# shinobi_environment.net
KiCad netlist of a schematic drawn in EAGLE
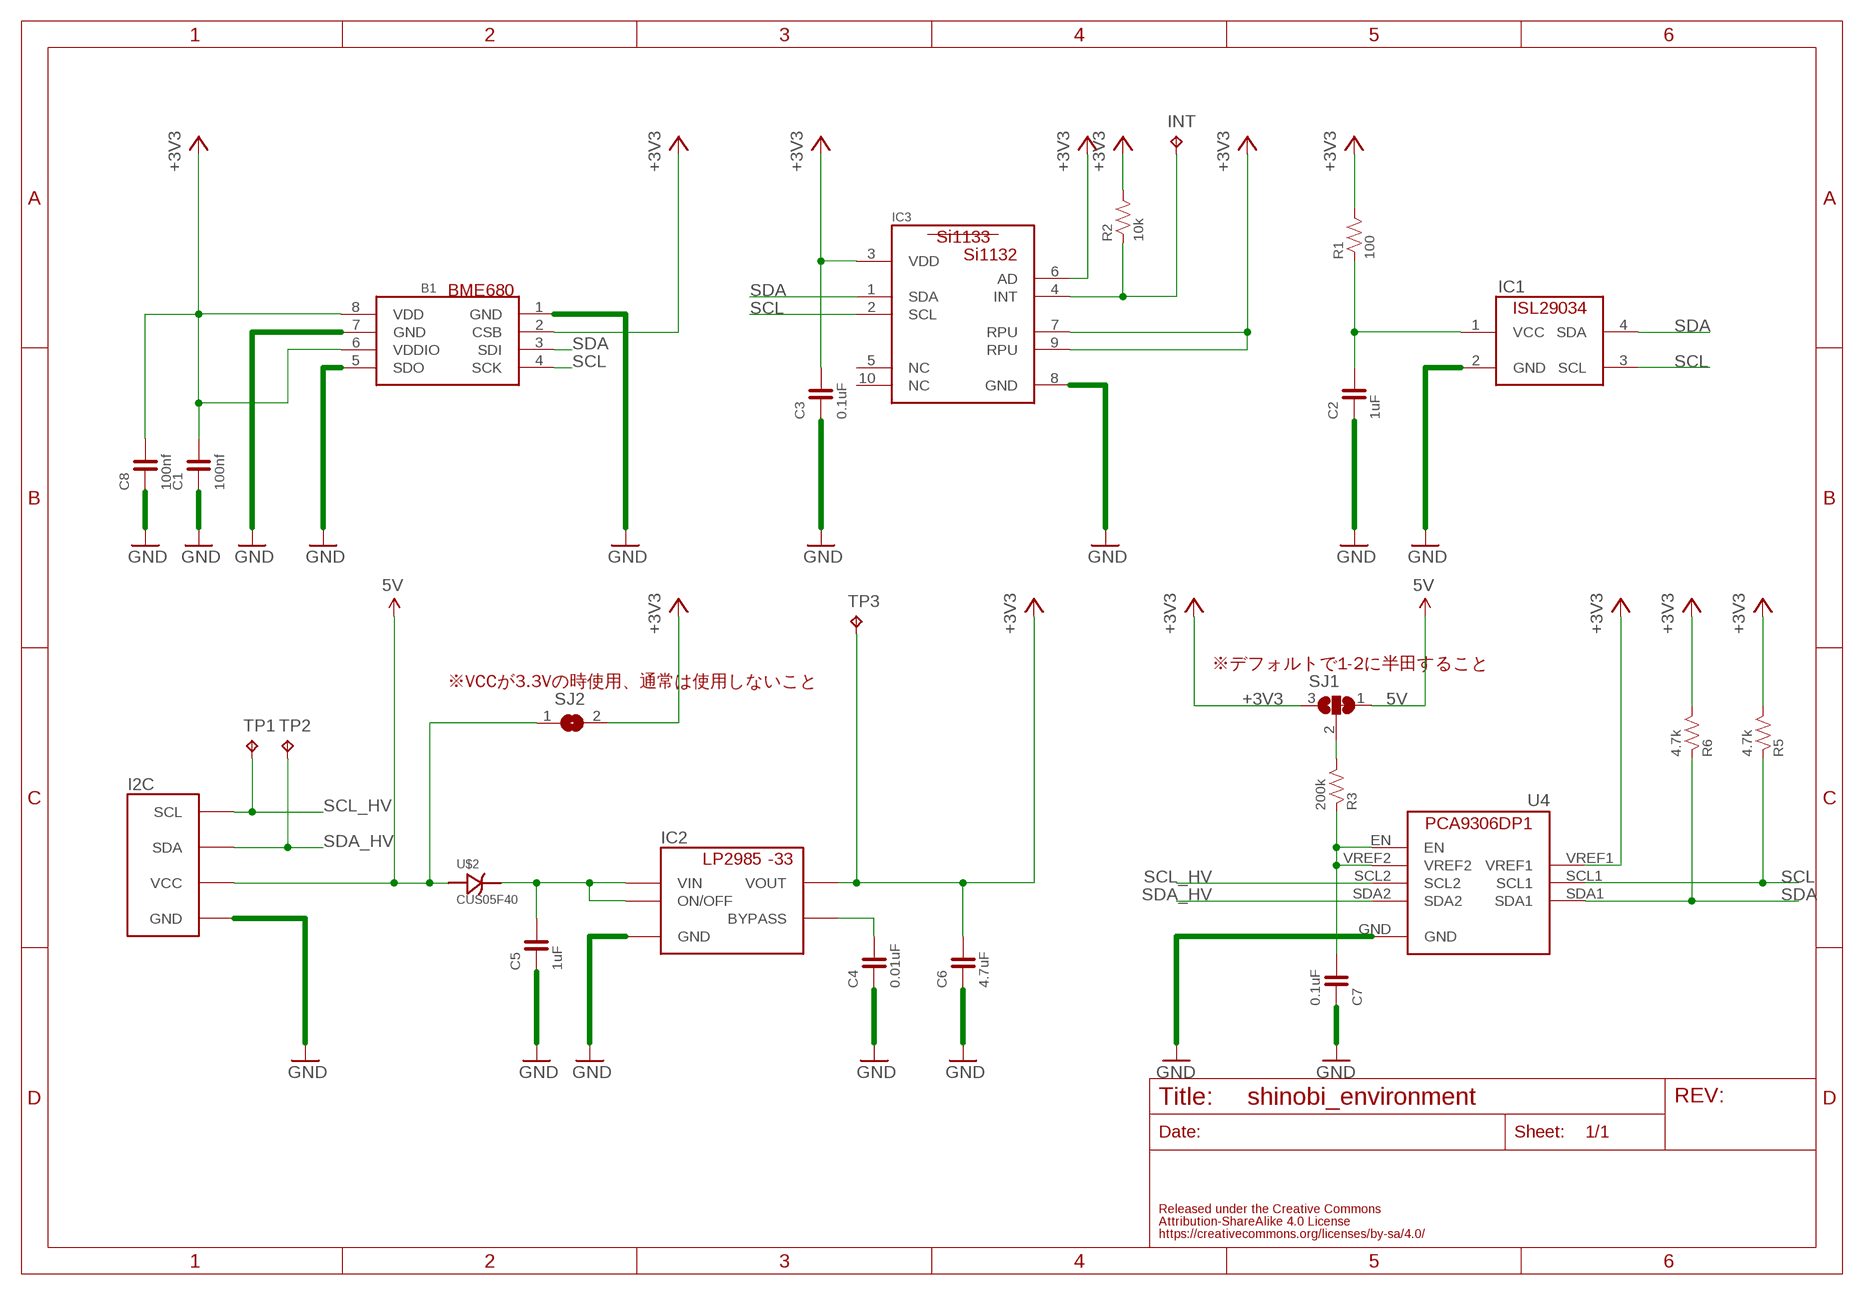
[diagram p0: schematic, sheet 1]

(export (version "E")
  (design (tool "Eeschema 10.0.6"))
  (components
    (comp (ref "B1")
      (value "BO-BME680")
      (footprint "eagle-import:BOSCH-BME680")
      (libsource (lib "eagle-import") (part "BO-BME680"))
    )
    (comp (ref "C1")
      (value "100nf")
      (footprint "eagle-import:0603")
      (libsource (lib "eagle-import") (part "CAPACITOR-0603"))
    )
    (comp (ref "C2")
      (value "1uF")
      (footprint "eagle-import:0603")
      (libsource (lib "eagle-import") (part "CAPACITOR-0603"))
    )
    (comp (ref "C3")
      (value "0.1uF")
      (footprint "eagle-import:0603")
      (libsource (lib "eagle-import") (part "CAPACITOR-0603"))
    )
    (comp (ref "C4")
      (value "0.01uF")
      (footprint "eagle-import:0603")
      (libsource (lib "eagle-import") (part "CAPACITOR-0603"))
    )
    (comp (ref "C5")
      (value "1uF")
      (footprint "eagle-import:0603")
      (libsource (lib "eagle-import") (part "CAPACITOR-0603"))
    )
    (comp (ref "C6")
      (value "4.7uF")
      (footprint "eagle-import:0603")
      (libsource (lib "eagle-import") (part "CAPACITOR-0603"))
    )
    (comp (ref "C7")
      (value "0.1uF")
      (footprint "eagle-import:0603")
      (libsource (lib "eagle-import") (part "CAPACITOR-0603"))
    )
    (comp (ref "C8")
      (value "100nf")
      (footprint "eagle-import:0603")
      (libsource (lib "eagle-import") (part "CAPACITOR-0603"))
    )
    (comp (ref "I2C")
      (value "FABO_BRICK_I2C-S04B-PASK-2_LONG")
      (footprint "eagle-import:FABO_BRICK_I2C_S04B-PASK-2_LONG")
      (libsource (lib "eagle-import") (part "FABO_BRICK_I2C-S04B-PASK-2_LONG"))
    )
    (comp (ref "IC1")
      (value "IN-ISL29034")
      (footprint "eagle-import:INTERSIL-ISL29034")
      (libsource (lib "eagle-import") (part "IN-ISL29034"))
    )
    (comp (ref "IC2")
      (value "LP2985-33DBV")
      (footprint "eagle-import:SOT-23-5")
      (libsource (lib "eagle-import") (part "LP2985-33DBV"))
    )
    (comp (ref "IC3")
      (value "SILICONLABS-SI1133")
      (footprint "eagle-import:SILICONLABS-SI1133")
      (libsource (lib "eagle-import") (part "SILICONLABS-SI1133"))
    )
    (comp (ref "INT")
      (value "TPB1,27")
      (footprint "eagle-import:B1,27")
      (libsource (lib "eagle-import") (part "TPB1,27"))
    )
    (comp (ref "R1")
      (value "100")
      (footprint "eagle-import:0603")
      (libsource (lib "eagle-import") (part "RESISTOR-0603"))
    )
    (comp (ref "R2")
      (value "10k")
      (footprint "eagle-import:0603")
      (libsource (lib "eagle-import") (part "RESISTOR-0603"))
    )
    (comp (ref "R3")
      (value "200k")
      (footprint "eagle-import:0603")
      (libsource (lib "eagle-import") (part "RESISTOR-0603"))
    )
    (comp (ref "R5")
      (value "4.7k")
      (footprint "eagle-import:0603")
      (libsource (lib "eagle-import") (part "RESISTOR-0603"))
    )
    (comp (ref "R6")
      (value "4.7k")
      (footprint "eagle-import:0603")
      (libsource (lib "eagle-import") (part "RESISTOR-0603"))
    )
    (comp (ref "SJ1")
      (value "SJ2W")
      (footprint "eagle-import:SJ_2")
      (libsource (lib "eagle-import") (part "SJ2W"))
    )
    (comp (ref "SJ2") (value "SJ") (footprint "eagle-import:SJ") (libsource (lib "eagle-import") (part "SJ")))
    (comp (ref "TP1")
      (value "TPB1,27")
      (footprint "eagle-import:B1,27")
      (libsource (lib "eagle-import") (part "TPB1,27"))
    )
    (comp (ref "TP2")
      (value "TPB1,27")
      (footprint "eagle-import:B1,27")
      (libsource (lib "eagle-import") (part "TPB1,27"))
    )
    (comp (ref "TP3")
      (value "TPB1,27")
      (footprint "eagle-import:B1,27")
      (libsource (lib "eagle-import") (part "TPB1,27"))
    )
    (comp (ref "U$2")
      (value "CUS05F40")
      (footprint "eagle-import:CUS05F40")
      (libsource (lib "eagle-import") (part "CUS05F40"))
    )
    (comp (ref "U4")
      (value "PCA9306DP1")
      (footprint "eagle-import:TSSOP8")
      (libsource (lib "eagle-import") (part "PCA9306DP1"))
    )
  )
  (nets
    (net (code "1") (name "+3V3") (class "Default")
      (node (ref "B1") (pin "2") (pinfunction "CSB_2") (pintype "bidirectional"))
      (node (ref "B1") (pin "6") (pinfunction "VDDIO_6") (pintype "bidirectional"))
      (node (ref "B1") (pin "8") (pinfunction "VDD_8") (pintype "bidirectional"))
      (node (ref "C1") (pin "2") (pinfunction "2_2") (pintype "passive"))
      (node (ref "C3") (pin "2") (pinfunction "2_2") (pintype "passive"))
      (node (ref "C6") (pin "2") (pinfunction "2_2") (pintype "passive"))
      (node (ref "C8") (pin "2") (pinfunction "2_2") (pintype "passive"))
      (node (ref "IC2") (pin "5") (pinfunction "VOUT_5") (pintype "output"))
      (node (ref "IC3") (pin "3") (pinfunction "VDD_3") (pintype "bidirectional"))
      (node (ref "IC3") (pin "6") (pinfunction "AD_6") (pintype "bidirectional"))
      (node (ref "IC3") (pin "7") (pinfunction "RPU_7") (pintype "bidirectional"))
      (node (ref "IC3") (pin "9") (pinfunction "RPU_9") (pintype "bidirectional"))
      (node (ref "R1") (pin "2") (pinfunction "2_2") (pintype "bidirectional"))
      (node (ref "R2") (pin "2") (pinfunction "2_2") (pintype "bidirectional"))
      (node (ref "R5") (pin "2") (pinfunction "2_2") (pintype "bidirectional"))
      (node (ref "R6") (pin "2") (pinfunction "2_2") (pintype "bidirectional"))
      (node (ref "SJ1") (pin "3") (pinfunction "3_3") (pintype "passive"))
      (node (ref "SJ2") (pin "2") (pinfunction "2_2") (pintype "passive"))
      (node (ref "TP3") (pin "TP") (pinfunction "TP_TP") (pintype "input"))
      (node (ref "U4") (pin "VREF1") (pinfunction "VREF1_VREF1") (pintype "bidirectional"))
    )
    (net (code "2") (name "/SCL") (class "Default")
      (node (ref "B1") (pin "4") (pinfunction "SCK_4") (pintype "bidirectional"))
      (node (ref "IC1") (pin "3") (pinfunction "SCL_3") (pintype "bidirectional"))
      (node (ref "IC3") (pin "2") (pinfunction "SCL_2") (pintype "bidirectional"))
      (node (ref "R5") (pin "1") (pinfunction "1_1") (pintype "bidirectional"))
      (node (ref "U4") (pin "SCL1") (pinfunction "SCL1_SCL1") (pintype "bidirectional"))
    )
    (net (code "3") (name "/SCL_HV") (class "Default")
      (node (ref "I2C") (pin "SCL") (pinfunction "SCL_SCL") (pintype "bidirectional"))
      (node (ref "TP1") (pin "TP") (pinfunction "TP_TP") (pintype "input"))
      (node (ref "U4") (pin "SCL2") (pinfunction "SCL2_SCL2") (pintype "bidirectional"))
    )
    (net (code "4") (name "/SDA") (class "Default")
      (node (ref "B1") (pin "3") (pinfunction "SDI_3") (pintype "bidirectional"))
      (node (ref "IC1") (pin "4") (pinfunction "SDA_4") (pintype "bidirectional"))
      (node (ref "IC3") (pin "1") (pinfunction "SDA_1") (pintype "bidirectional"))
      (node (ref "R6") (pin "1") (pinfunction "1_1") (pintype "bidirectional"))
      (node (ref "U4") (pin "SDA1") (pinfunction "SDA1_SDA1") (pintype "bidirectional"))
    )
    (net (code "5") (name "/SDA_HV") (class "Default")
      (node (ref "I2C") (pin "SDA") (pinfunction "SDA_SDA") (pintype "bidirectional"))
      (node (ref "TP2") (pin "TP") (pinfunction "TP_TP") (pintype "input"))
      (node (ref "U4") (pin "SDA2") (pinfunction "SDA2_SDA2") (pintype "bidirectional"))
    )
    (net (code "6") (name "5V") (class "Default")
      (node (ref "I2C") (pin "VCC") (pinfunction "VCC_VCC") (pintype "bidirectional"))
      (node (ref "SJ1") (pin "1") (pinfunction "1_1") (pintype "passive"))
      (node (ref "SJ2") (pin "1") (pinfunction "1_1") (pintype "passive"))
      (node (ref "U$2") (pin "A") (pinfunction "ANODE_A") (pintype "bidirectional"))
    )
    (net (code "7") (name "GND") (class "Default")
      (node (ref "B1") (pin "1") (pinfunction "GND_1") (pintype "bidirectional"))
      (node (ref "B1") (pin "5") (pinfunction "SDO_5") (pintype "bidirectional"))
      (node (ref "B1") (pin "7") (pinfunction "GND_7") (pintype "bidirectional"))
      (node (ref "C1") (pin "1") (pinfunction "1_1") (pintype "passive"))
      (node (ref "C2") (pin "1") (pinfunction "1_1") (pintype "passive"))
      (node (ref "C3") (pin "1") (pinfunction "1_1") (pintype "passive"))
      (node (ref "C4") (pin "1") (pinfunction "1_1") (pintype "passive"))
      (node (ref "C5") (pin "1") (pinfunction "1_1") (pintype "passive"))
      (node (ref "C6") (pin "1") (pinfunction "1_1") (pintype "passive"))
      (node (ref "C7") (pin "1") (pinfunction "1_1") (pintype "passive"))
      (node (ref "C8") (pin "1") (pinfunction "1_1") (pintype "passive"))
      (node (ref "I2C") (pin "GND") (pinfunction "GND_GND") (pintype "bidirectional"))
      (node (ref "IC1") (pin "2") (pinfunction "GND_2") (pintype "bidirectional"))
      (node (ref "IC2") (pin "2") (pinfunction "GND_2") (pintype "power_in"))
      (node (ref "IC3") (pin "8") (pinfunction "GND_8") (pintype "bidirectional"))
      (node (ref "U4") (pin "GND") (pinfunction "GND_GND") (pintype "bidirectional"))
    )
    (net (code "8") (name "Net-(C7-Pad2)") (class "Default")
      (node (ref "C7") (pin "2") (pinfunction "2_2") (pintype "passive"))
      (node (ref "R3") (pin "1") (pinfunction "1_1") (pintype "bidirectional"))
      (node (ref "U4") (pin "EN") (pinfunction "EN_EN") (pintype "bidirectional"))
      (node (ref "U4") (pin "VREF2") (pinfunction "VREF2_VREF2") (pintype "bidirectional"))
    )
    (net (code "9") (name "Net-(IC1-VCC)") (class "Default")
      (node (ref "C2") (pin "2") (pinfunction "2_2") (pintype "passive"))
      (node (ref "IC1") (pin "1") (pinfunction "VCC_1") (pintype "bidirectional"))
      (node (ref "R1") (pin "1") (pinfunction "1_1") (pintype "bidirectional"))
    )
    (net (code "10") (name "Net-(IC2-BYPASS)") (class "Default")
      (node (ref "C4") (pin "2") (pinfunction "2_2") (pintype "passive"))
      (node (ref "IC2") (pin "4") (pinfunction "BYPASS_4") (pintype "bidirectional"))
    )
    (net (code "11") (name "Net-(IC2-ON{slash}OFF)") (class "Default")
      (node (ref "C5") (pin "2") (pinfunction "2_2") (pintype "passive"))
      (node (ref "IC2") (pin "1") (pinfunction "VIN_1") (pintype "input"))
      (node (ref "IC2") (pin "3") (pinfunction "ON/OFF_3") (pintype "input"))
      (node (ref "U$2") (pin "C") (pinfunction "CATHODE_C") (pintype "bidirectional"))
    )
    (net (code "12") (name "Net-(IC3-INT)") (class "Default")
      (node (ref "IC3") (pin "4") (pinfunction "INT_4") (pintype "bidirectional"))
      (node (ref "INT") (pin "TP") (pinfunction "TP_TP") (pintype "input"))
      (node (ref "R2") (pin "1") (pinfunction "1_1") (pintype "bidirectional"))
    )
    (net (code "13") (name "Net-(R3-Pad2)") (class "Default")
      (node (ref "R3") (pin "2") (pinfunction "2_2") (pintype "bidirectional"))
      (node (ref "SJ1") (pin "2") (pinfunction "2_2") (pintype "passive"))
    )
    (net (code "14") (name "unconnected-(IC3-NC-Pad5)") (class "Default")
      (node (ref "IC3") (pin "5") (pinfunction "NC_5") (pintype "bidirectional"))
    )
    (net (code "15") (name "unconnected-(IC3-NC-Pad10)") (class "Default")
      (node (ref "IC3") (pin "10") (pinfunction "NC_10") (pintype "bidirectional"))
    )
  )
)
